# connector.net
KiCad netlist of a schematic drawn in Altium Designer
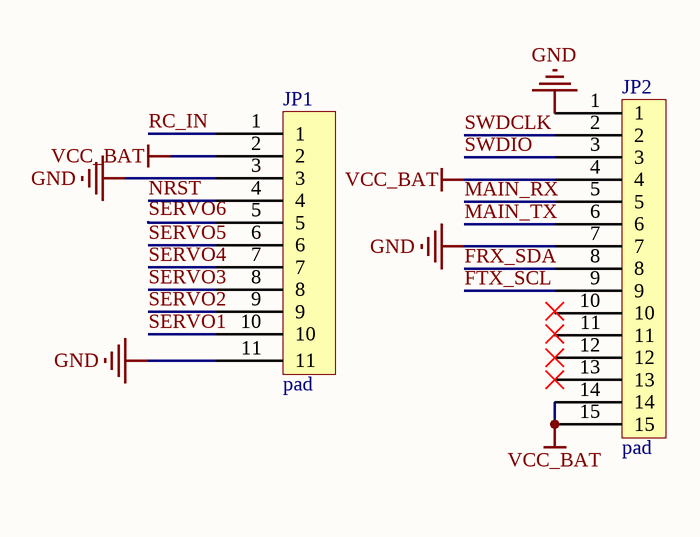
[diagram p0: connector.SchDoc]

(export (version "E")
  (design (tool "Eeschema 10.0.6"))
  (components
    (comp (ref "JP1")
      (value "pad")
      (footprint "1.27*11")
      (description "11pin pad")
      (libsource (lib "sparky") (part "1.27*11"))
    )
    (comp (ref "JP2")
      (value "pad")
      (footprint "1.27*15")
      (description "15pin pad")
      (libsource (lib "sparky") (part "1.27*15"))
    )
  )
  (nets
    (net (code "1") (name "/FRX_SDA") (class "Default")
      (node (ref "JP2") (pin "8") (pinfunction "8_8") (pintype "passive"))
    )
    (net (code "2") (name "/FTX_SCL") (class "Default")
      (node (ref "JP2") (pin "9") (pinfunction "9_9") (pintype "passive"))
    )
    (net (code "3") (name "/MAIN_RX") (class "Default")
      (node (ref "JP2") (pin "5") (pinfunction "5_5") (pintype "passive"))
    )
    (net (code "4") (name "/MAIN_TX") (class "Default")
      (node (ref "JP2") (pin "6") (pinfunction "6_6") (pintype "passive"))
    )
    (net (code "5") (name "/NRST") (class "Default")
      (node (ref "JP1") (pin "4") (pinfunction "4_4") (pintype "passive"))
    )
    (net (code "6") (name "/RC_IN") (class "Default")
      (node (ref "JP1") (pin "1") (pinfunction "1_1") (pintype "passive"))
    )
    (net (code "7") (name "/SERVO1") (class "Default")
      (node (ref "JP1") (pin "10") (pinfunction "10_10") (pintype "passive"))
    )
    (net (code "8") (name "/SERVO2") (class "Default")
      (node (ref "JP1") (pin "9") (pinfunction "9_9") (pintype "passive"))
    )
    (net (code "9") (name "/SERVO3") (class "Default")
      (node (ref "JP1") (pin "8") (pinfunction "8_8") (pintype "passive"))
    )
    (net (code "10") (name "/SERVO4") (class "Default")
      (node (ref "JP1") (pin "7") (pinfunction "7_7") (pintype "passive"))
    )
    (net (code "11") (name "/SERVO5") (class "Default")
      (node (ref "JP1") (pin "6") (pinfunction "6_6") (pintype "passive"))
    )
    (net (code "12") (name "/SERVO6") (class "Default")
      (node (ref "JP1") (pin "5") (pinfunction "5_5") (pintype "passive"))
    )
    (net (code "13") (name "/SWDCLK") (class "Default")
      (node (ref "JP2") (pin "2") (pinfunction "2_2") (pintype "passive"))
    )
    (net (code "14") (name "/SWDIO") (class "Default")
      (node (ref "JP2") (pin "3") (pinfunction "3_3") (pintype "passive"))
    )
    (net (code "15") (name "GND") (class "Default")
      (node (ref "JP1") (pin "11") (pinfunction "11_11") (pintype "passive"))
      (node (ref "JP1") (pin "3") (pinfunction "3_3") (pintype "passive"))
      (node (ref "JP2") (pin "1") (pinfunction "1_1") (pintype "passive"))
      (node (ref "JP2") (pin "7") (pinfunction "7_7") (pintype "passive"))
    )
    (net (code "16") (name "VCC_BAT") (class "Default")
      (node (ref "JP1") (pin "2") (pinfunction "2_2") (pintype "passive"))
      (node (ref "JP2") (pin "14") (pinfunction "14_14") (pintype "passive"))
      (node (ref "JP2") (pin "15") (pinfunction "15_15") (pintype "passive"))
      (node (ref "JP2") (pin "4") (pinfunction "4_4") (pintype "passive"))
    )
    (net (code "17") (name "unconnected-(JP2-Pad10)") (class "Default")
      (node (ref "JP2") (pin "10") (pinfunction "10_10") (pintype "passive"))
    )
    (net (code "18") (name "unconnected-(JP2-Pad11)") (class "Default")
      (node (ref "JP2") (pin "11") (pinfunction "11_11") (pintype "passive"))
    )
    (net (code "19") (name "unconnected-(JP2-Pad12)") (class "Default")
      (node (ref "JP2") (pin "12") (pinfunction "12_12") (pintype "passive+no_connect"))
    )
    (net (code "20") (name "unconnected-(JP2-Pad13)") (class "Default")
      (node (ref "JP2") (pin "13") (pinfunction "13_13") (pintype "passive+no_connect"))
    )
  )
)
